# 4robots_MAIN_1_1.net
KiCad netlist of a schematic drawn in EAGLE
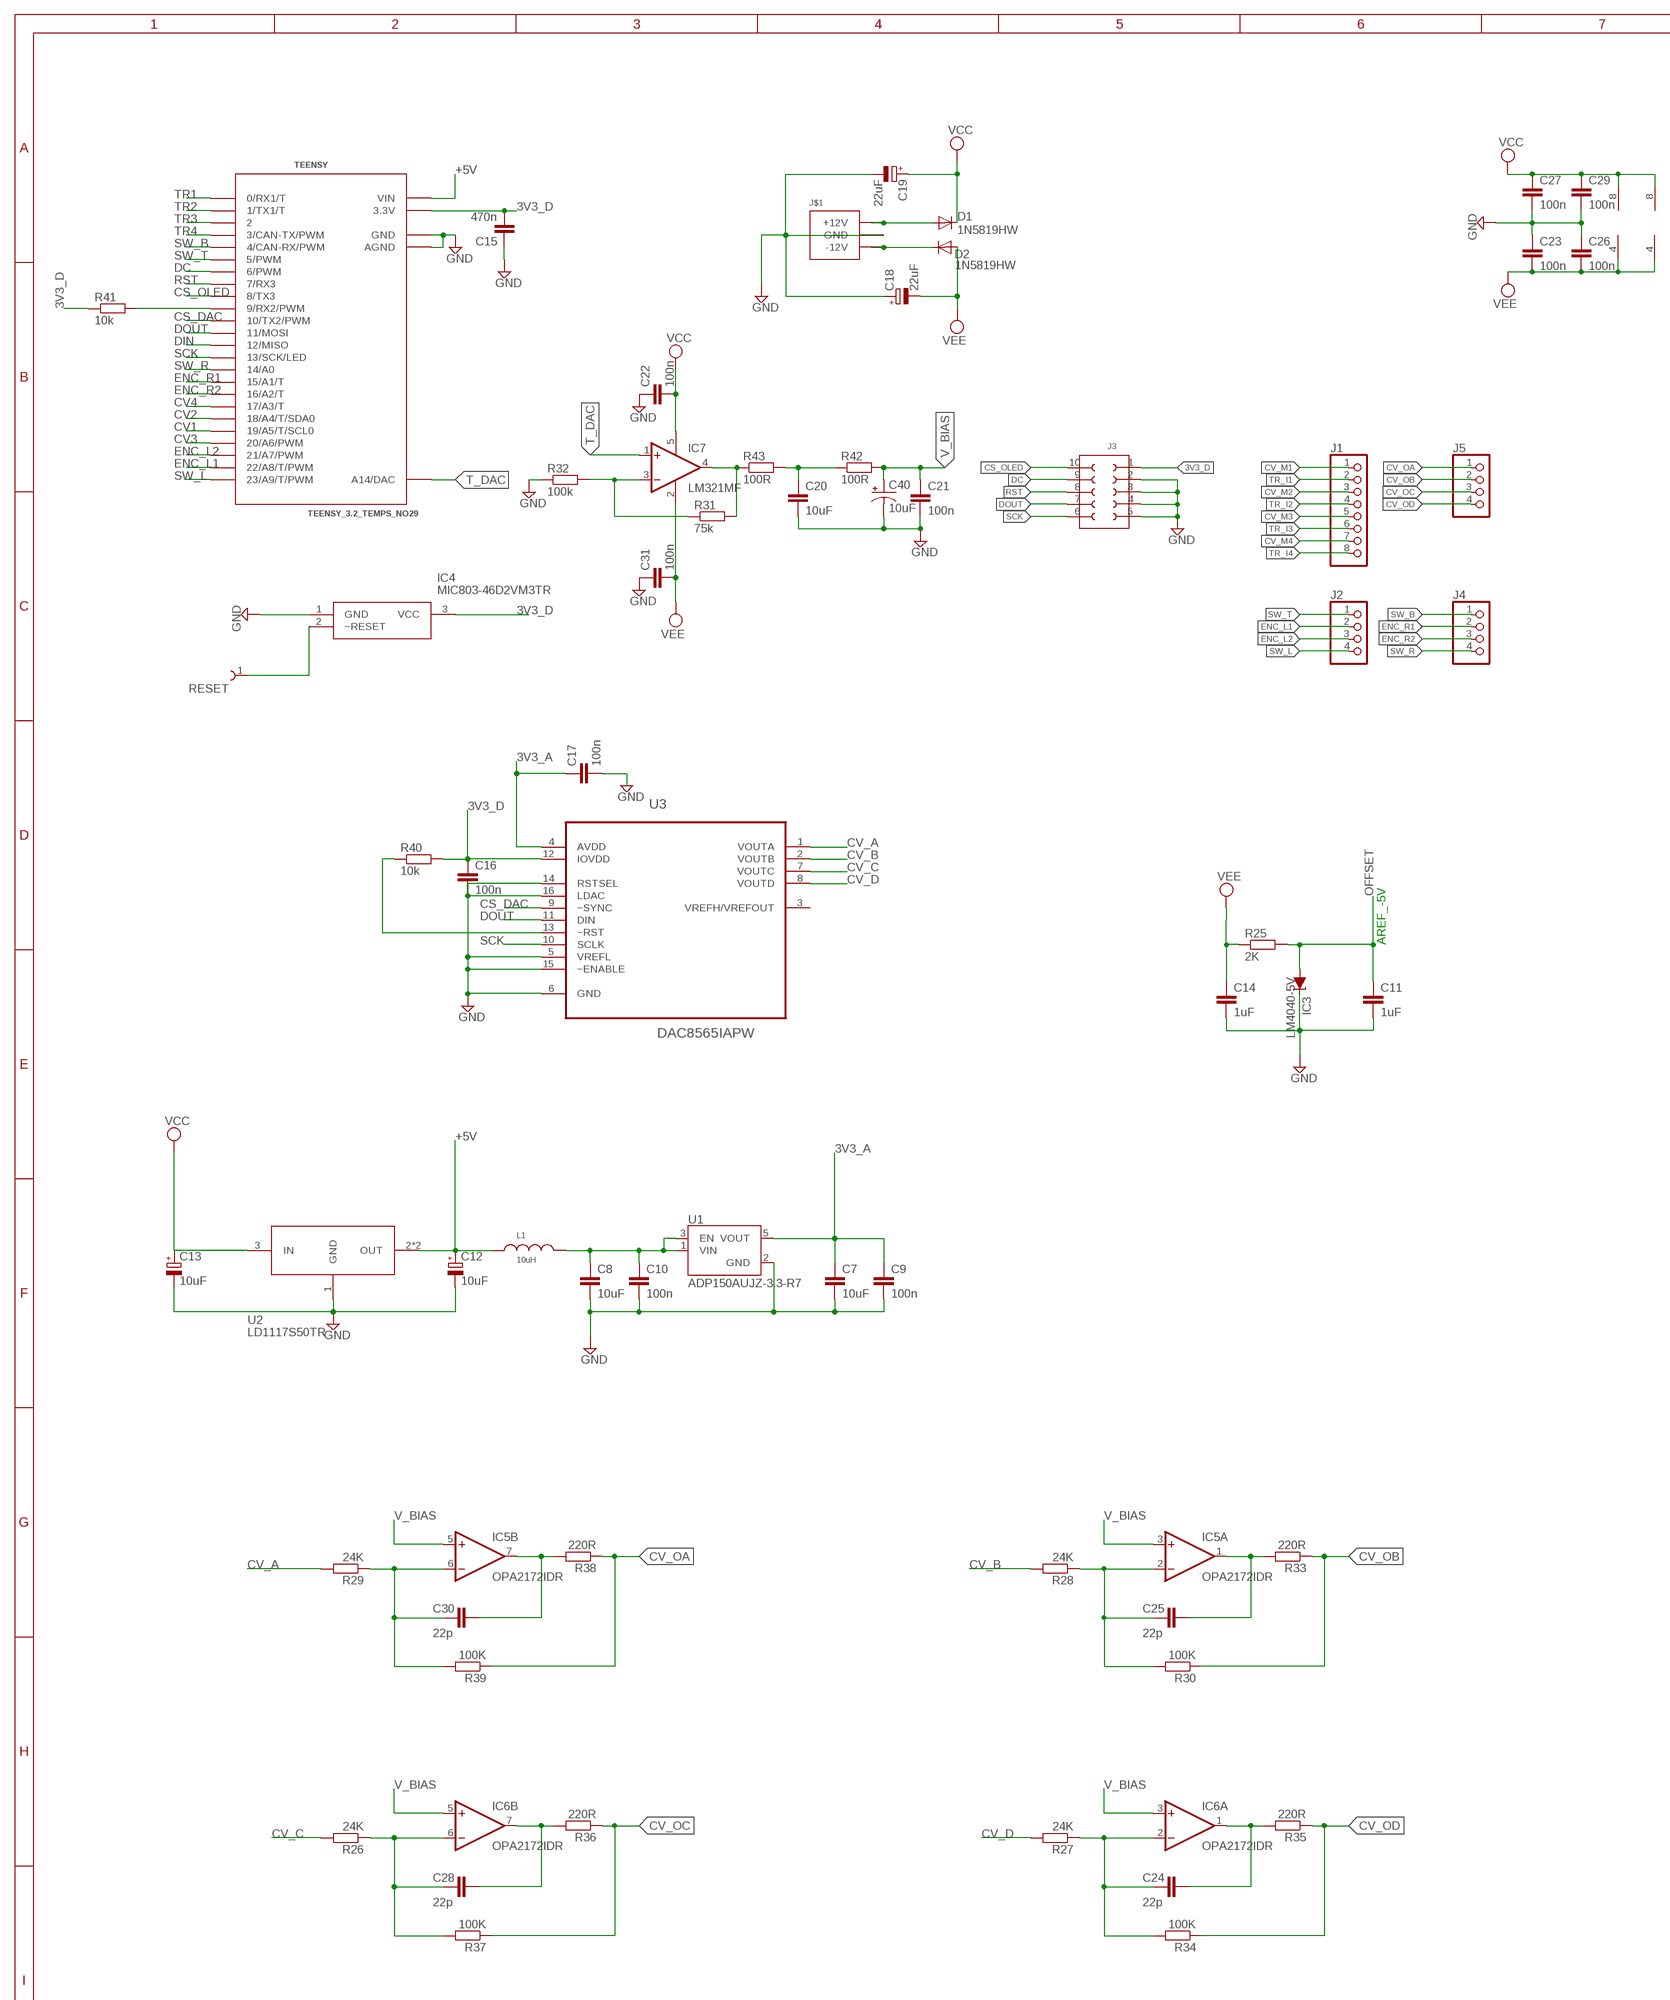
[diagram p0: schematic, sheet 1, part 1 of 2]
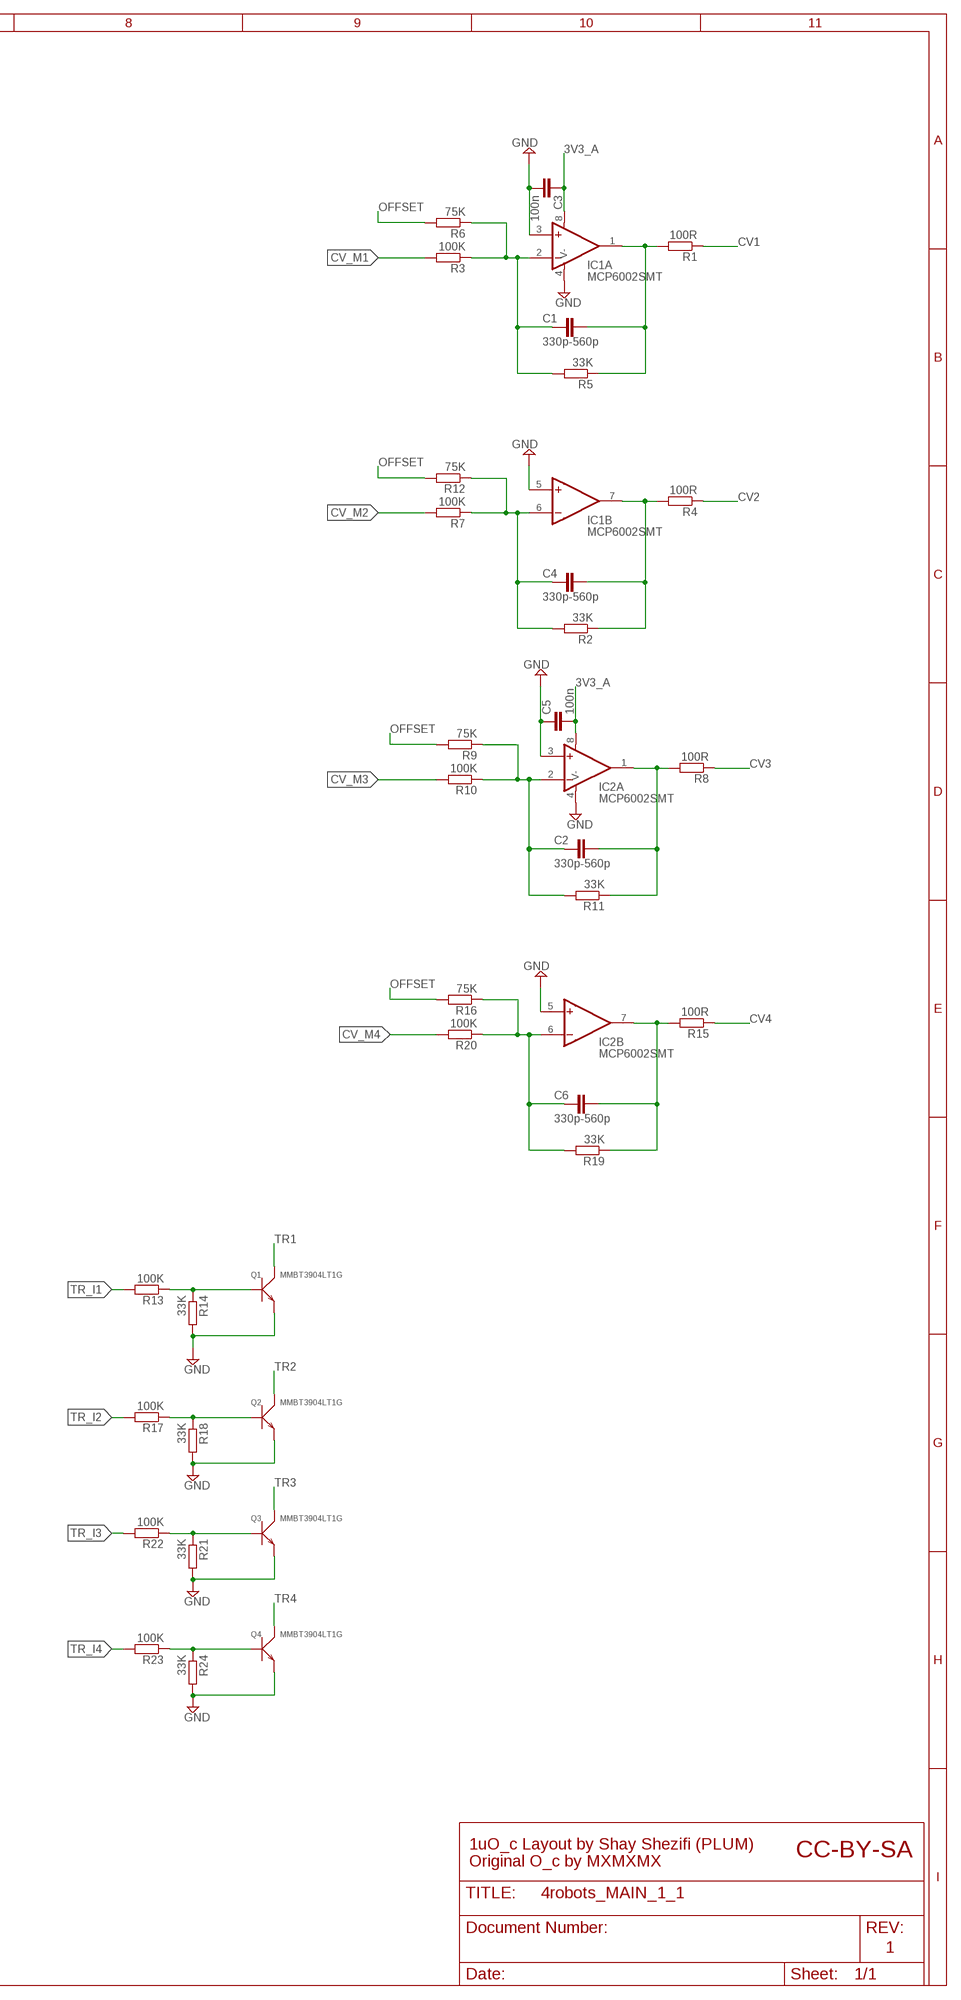
[diagram p1: schematic, sheet 1, part 2 of 2]

(export (version "E")
  (design (tool "Eeschema 10.0.6"))
  (components
    (comp (ref "C1")
      (value "330p-560p")
      (footprint "eagle-import:C0603")
      (libsource (lib "eagle-import") (part "C-EUC0603"))
    )
    (comp (ref "C2")
      (value "330p-560p")
      (footprint "eagle-import:C0603")
      (libsource (lib "eagle-import") (part "C-EUC0603"))
    )
    (comp (ref "C3")
      (value "100n")
      (footprint "eagle-import:C0603")
      (libsource (lib "eagle-import") (part "C-EUC0603"))
    )
    (comp (ref "C4")
      (value "330p-560p")
      (footprint "eagle-import:C0603")
      (libsource (lib "eagle-import") (part "C-EUC0603"))
    )
    (comp (ref "C5")
      (value "100n")
      (footprint "eagle-import:C0603")
      (libsource (lib "eagle-import") (part "C-EUC0603"))
    )
    (comp (ref "C6")
      (value "330p-560p")
      (footprint "eagle-import:C0603")
      (libsource (lib "eagle-import") (part "C-EUC0603"))
    )
    (comp (ref "C7")
      (value "10uF")
      (footprint "eagle-import:C1206K")
      (libsource (lib "eagle-import") (part "C-EUC1206K"))
    )
    (comp (ref "C8")
      (value "10uF")
      (footprint "eagle-import:C1206K")
      (libsource (lib "eagle-import") (part "C-EUC1206K"))
    )
    (comp (ref "C9")
      (value "100n")
      (footprint "eagle-import:C0603")
      (libsource (lib "eagle-import") (part "C-EUC0603"))
    )
    (comp (ref "C10")
      (value "100n")
      (footprint "eagle-import:C0603")
      (libsource (lib "eagle-import") (part "C-EUC0603"))
    )
    (comp (ref "C11")
      (value "1uF")
      (footprint "eagle-import:C0603")
      (libsource (lib "eagle-import") (part "C-EUC0603"))
    )
    (comp (ref "C12")
      (value "10uF")
      (footprint "eagle-import:PANASONIC_B")
      (libsource (lib "eagle-import") (part "CPOL-EUB"))
    )
    (comp (ref "C13")
      (value "10uF")
      (footprint "eagle-import:PANASONIC_B")
      (libsource (lib "eagle-import") (part "CPOL-EUB"))
    )
    (comp (ref "C14")
      (value "1uF")
      (footprint "eagle-import:C0603")
      (libsource (lib "eagle-import") (part "C-EUC0603"))
    )
    (comp (ref "C15")
      (value "470n")
      (footprint "eagle-import:C0603")
      (libsource (lib "eagle-import") (part "C-EUC0603"))
    )
    (comp (ref "C16")
      (value "100n")
      (footprint "eagle-import:C0603")
      (libsource (lib "eagle-import") (part "C-EUC0603"))
    )
    (comp (ref "C17")
      (value "100n")
      (footprint "eagle-import:C0603")
      (libsource (lib "eagle-import") (part "C-EUC0603"))
    )
    (comp (ref "C18")
      (value "22uF")
      (footprint "eagle-import:PANASONIC_C")
      (libsource (lib "eagle-import") (part "CPOL-EUC"))
    )
    (comp (ref "C19")
      (value "22uF")
      (footprint "eagle-import:PANASONIC_C")
      (libsource (lib "eagle-import") (part "CPOL-EUC"))
    )
    (comp (ref "C20")
      (value "10uF")
      (footprint "eagle-import:C0603")
      (libsource (lib "eagle-import") (part "C-EUC0603"))
    )
    (comp (ref "C21")
      (value "100n")
      (footprint "eagle-import:C0603")
      (libsource (lib "eagle-import") (part "C-EUC0603"))
    )
    (comp (ref "C22")
      (value "100n")
      (footprint "eagle-import:C0603")
      (libsource (lib "eagle-import") (part "C-EUC0603"))
    )
    (comp (ref "C23")
      (value "100n")
      (footprint "eagle-import:C0603")
      (libsource (lib "eagle-import") (part "C-EUC0603"))
    )
    (comp (ref "C24")
      (value "22p")
      (footprint "eagle-import:C0603")
      (libsource (lib "eagle-import") (part "C-EUC0603"))
    )
    (comp (ref "C25")
      (value "22p")
      (footprint "eagle-import:C0603")
      (libsource (lib "eagle-import") (part "C-EUC0603"))
    )
    (comp (ref "C26")
      (value "100n")
      (footprint "eagle-import:C0603")
      (libsource (lib "eagle-import") (part "C-EUC0603"))
    )
    (comp (ref "C27")
      (value "100n")
      (footprint "eagle-import:C0603")
      (libsource (lib "eagle-import") (part "C-EUC0603"))
    )
    (comp (ref "C28")
      (value "22p")
      (footprint "eagle-import:C0603")
      (libsource (lib "eagle-import") (part "C-EUC0603"))
    )
    (comp (ref "C29")
      (value "100n")
      (footprint "eagle-import:C0603")
      (libsource (lib "eagle-import") (part "C-EUC0603"))
    )
    (comp (ref "C30")
      (value "22p")
      (footprint "eagle-import:C0603")
      (libsource (lib "eagle-import") (part "C-EUC0603"))
    )
    (comp (ref "C31")
      (value "100n")
      (footprint "eagle-import:C0603")
      (libsource (lib "eagle-import") (part "C-EUC0603"))
    )
    (comp (ref "C40")
      (value "10uF")
      (footprint "eagle-import:PANASONIC_A")
      (libsource (lib "eagle-import") (part "CPOL-USA"))
    )
    (comp (ref "D1")
      (value "1N5819HW")
      (footprint "eagle-import:DIODE_SOD123")
      (libsource (lib "eagle-import") (part "DIODE_DIODE-SOD123"))
    )
    (comp (ref "D2")
      (value "1N5819HW")
      (footprint "eagle-import:DIODE_SOD123")
      (libsource (lib "eagle-import") (part "DIODE_DIODE-SOD123"))
    )
    (comp (ref "IC1")
      (value "MCP6002SMT")
      (footprint "eagle-import:SOIC8")
      (libsource (lib "eagle-import") (part "MCP6002SMT"))
    )
    (comp (ref "IC2")
      (value "MCP6002SMT")
      (footprint "eagle-import:SOIC8")
      (libsource (lib "eagle-import") (part "MCP6002SMT"))
    )
    (comp (ref "IC3")
      (value "LM4040-5V")
      (footprint "eagle-import:DBZ_R-PDSO-G3")
      (libsource (lib "eagle-import") (part "LM4041DBZB12"))
    )
    (comp (ref "IC4")
      (value "MIC803-46D2VM3TR")
      (footprint "eagle-import:SOT95P230X110-3N")
      (libsource (lib "eagle-import") (part "MIC803-46D2VM3TR"))
    )
    (comp (ref "IC5")
      (value "OPA2172IDR")
      (footprint "eagle-import:SO08")
      (libsource (lib "eagle-import") (part "TL072D"))
    )
    (comp (ref "IC6")
      (value "OPA2172IDR")
      (footprint "eagle-import:SO08")
      (libsource (lib "eagle-import") (part "TL072D"))
    )
    (comp (ref "IC7")
      (value "LM321MF")
      (footprint "eagle-import:SOT23-5")
      (libsource (lib "eagle-import") (part "LM321?MF"))
    )
    (comp (ref "J$1")
      (value "POWER_SIMPLE10")
      (footprint "eagle-import:POWER_10")
      (libsource (lib "eagle-import") (part "POWER_SIMPLE10"))
    )
    (comp (ref "J1")
      (value "PINHD-1X8")
      (footprint "eagle-import:1X08")
      (libsource (lib "eagle-import") (part "PINHD-1X8"))
    )
    (comp (ref "J2")
      (value "PINHD-1X4")
      (footprint "eagle-import:1X04")
      (libsource (lib "eagle-import") (part "PINHD-1X4"))
    )
    (comp (ref "J3")
      (value "61301021121")
      (footprint "eagle-import:61301021121")
      (libsource (lib "eagle-import") (part "61301021121"))
    )
    (comp (ref "J4")
      (value "PINHD-1X4")
      (footprint "eagle-import:1X04")
      (libsource (lib "eagle-import") (part "PINHD-1X4"))
    )
    (comp (ref "J5")
      (value "PINHD-1X4")
      (footprint "eagle-import:1X04")
      (libsource (lib "eagle-import") (part "PINHD-1X4"))
    )
    (comp (ref "L1")
      (value "10uH")
      (footprint "eagle-import:WE-LQ_M")
      (libsource (lib "eagle-import") (part "WE-LQ_1210_744032001"))
    )
    (comp (ref "Q1")
      (value "MMBT3904LT1G")
      (footprint "eagle-import:SOT-23")
      (libsource (lib "eagle-import") (part "SMD-TRANSISTORS-NPN-40V-200MA-MMBT3904LT1G(SOT-23)"))
    )
    (comp (ref "Q2")
      (value "MMBT3904LT1G")
      (footprint "eagle-import:SOT-23")
      (libsource (lib "eagle-import") (part "SMD-TRANSISTORS-NPN-40V-200MA-MMBT3904LT1G(SOT-23)"))
    )
    (comp (ref "Q3")
      (value "MMBT3904LT1G")
      (footprint "eagle-import:SOT-23")
      (libsource (lib "eagle-import") (part "SMD-TRANSISTORS-NPN-40V-200MA-MMBT3904LT1G(SOT-23)"))
    )
    (comp (ref "Q4")
      (value "MMBT3904LT1G")
      (footprint "eagle-import:SOT-23")
      (libsource (lib "eagle-import") (part "SMD-TRANSISTORS-NPN-40V-200MA-MMBT3904LT1G(SOT-23)"))
    )
    (comp (ref "R1")
      (value "100R")
      (footprint "eagle-import:R0603")
      (libsource (lib "eagle-import") (part "R-EU_R0603"))
    )
    (comp (ref "R2")
      (value "33K")
      (footprint "eagle-import:R0603")
      (libsource (lib "eagle-import") (part "R-EU_R0603"))
    )
    (comp (ref "R3")
      (value "100K")
      (footprint "eagle-import:R0603")
      (libsource (lib "eagle-import") (part "R-EU_R0603"))
    )
    (comp (ref "R4")
      (value "100R")
      (footprint "eagle-import:R0603")
      (libsource (lib "eagle-import") (part "R-EU_R0603"))
    )
    (comp (ref "R5")
      (value "33K")
      (footprint "eagle-import:R0603")
      (libsource (lib "eagle-import") (part "R-EU_R0603"))
    )
    (comp (ref "R6")
      (value "75K")
      (footprint "eagle-import:R0603")
      (libsource (lib "eagle-import") (part "R-EU_R0603"))
    )
    (comp (ref "R7")
      (value "100K")
      (footprint "eagle-import:R0603")
      (libsource (lib "eagle-import") (part "R-EU_R0603"))
    )
    (comp (ref "R8")
      (value "100R")
      (footprint "eagle-import:R0603")
      (libsource (lib "eagle-import") (part "R-EU_R0603"))
    )
    (comp (ref "R9")
      (value "75K")
      (footprint "eagle-import:R0603")
      (libsource (lib "eagle-import") (part "R-EU_R0603"))
    )
    (comp (ref "R10")
      (value "100K")
      (footprint "eagle-import:R0603")
      (libsource (lib "eagle-import") (part "R-EU_R0603"))
    )
    (comp (ref "R11")
      (value "33K")
      (footprint "eagle-import:R0603")
      (libsource (lib "eagle-import") (part "R-EU_R0603"))
    )
    (comp (ref "R12")
      (value "75K")
      (footprint "eagle-import:R0603")
      (libsource (lib "eagle-import") (part "R-EU_R0603"))
    )
    (comp (ref "R13")
      (value "100K")
      (footprint "eagle-import:R0603")
      (libsource (lib "eagle-import") (part "R-EU_R0603"))
    )
    (comp (ref "R14")
      (value "33K")
      (footprint "eagle-import:R0603")
      (libsource (lib "eagle-import") (part "R-EU_R0603"))
    )
    (comp (ref "R15")
      (value "100R")
      (footprint "eagle-import:R0603")
      (libsource (lib "eagle-import") (part "R-EU_R0603"))
    )
    (comp (ref "R16")
      (value "75K")
      (footprint "eagle-import:R0603")
      (libsource (lib "eagle-import") (part "R-EU_R0603"))
    )
    (comp (ref "R17")
      (value "100K")
      (footprint "eagle-import:R0603")
      (libsource (lib "eagle-import") (part "R-EU_R0603"))
    )
    (comp (ref "R18")
      (value "33K")
      (footprint "eagle-import:R0603")
      (libsource (lib "eagle-import") (part "R-EU_R0603"))
    )
    (comp (ref "R19")
      (value "33K")
      (footprint "eagle-import:R0603")
      (libsource (lib "eagle-import") (part "R-EU_R0603"))
    )
    (comp (ref "R20")
      (value "100K")
      (footprint "eagle-import:R0603")
      (libsource (lib "eagle-import") (part "R-EU_R0603"))
    )
    (comp (ref "R21")
      (value "33K")
      (footprint "eagle-import:R0603")
      (libsource (lib "eagle-import") (part "R-EU_R0603"))
    )
    (comp (ref "R22")
      (value "100K")
      (footprint "eagle-import:R0603")
      (libsource (lib "eagle-import") (part "R-EU_R0603"))
    )
    (comp (ref "R23")
      (value "100K")
      (footprint "eagle-import:R0603")
      (libsource (lib "eagle-import") (part "R-EU_R0603"))
    )
    (comp (ref "R24")
      (value "33K")
      (footprint "eagle-import:R0603")
      (libsource (lib "eagle-import") (part "R-EU_R0603"))
    )
    (comp (ref "R25")
      (value "2K")
      (footprint "eagle-import:R0603")
      (libsource (lib "eagle-import") (part "R-EU_R0603"))
    )
    (comp (ref "R26")
      (value "24K")
      (footprint "eagle-import:R0603")
      (libsource (lib "eagle-import") (part "R-EU_R0603"))
    )
    (comp (ref "R27")
      (value "24K")
      (footprint "eagle-import:R0603")
      (libsource (lib "eagle-import") (part "R-EU_R0603"))
    )
    (comp (ref "R28")
      (value "24K")
      (footprint "eagle-import:R0603")
      (libsource (lib "eagle-import") (part "R-EU_R0603"))
    )
    (comp (ref "R29")
      (value "24K")
      (footprint "eagle-import:R0603")
      (libsource (lib "eagle-import") (part "R-EU_R0603"))
    )
    (comp (ref "R30")
      (value "100K")
      (footprint "eagle-import:R0603")
      (libsource (lib "eagle-import") (part "R-EU_R0603"))
    )
    (comp (ref "R31")
      (value "75k")
      (footprint "eagle-import:R0603")
      (libsource (lib "eagle-import") (part "R-EU_R0603"))
    )
    (comp (ref "R32")
      (value "100k")
      (footprint "eagle-import:R0603")
      (libsource (lib "eagle-import") (part "R-EU_R0603"))
    )
    (comp (ref "R33")
      (value "220R")
      (footprint "eagle-import:R0603")
      (libsource (lib "eagle-import") (part "R-EU_R0603"))
    )
    (comp (ref "R34")
      (value "100K")
      (footprint "eagle-import:R0603")
      (libsource (lib "eagle-import") (part "R-EU_R0603"))
    )
    (comp (ref "R35")
      (value "220R")
      (footprint "eagle-import:R0603")
      (libsource (lib "eagle-import") (part "R-EU_R0603"))
    )
    (comp (ref "R36")
      (value "220R")
      (footprint "eagle-import:R0603")
      (libsource (lib "eagle-import") (part "R-EU_R0603"))
    )
    (comp (ref "R37")
      (value "100K")
      (footprint "eagle-import:R0603")
      (libsource (lib "eagle-import") (part "R-EU_R0603"))
    )
    (comp (ref "R38")
      (value "220R")
      (footprint "eagle-import:R0603")
      (libsource (lib "eagle-import") (part "R-EU_R0603"))
    )
    (comp (ref "R39")
      (value "100K")
      (footprint "eagle-import:R0603")
      (libsource (lib "eagle-import") (part "R-EU_R0603"))
    )
    (comp (ref "R40")
      (value "10k")
      (footprint "eagle-import:R0603")
      (libsource (lib "eagle-import") (part "R-EU_R0603"))
    )
    (comp (ref "R41")
      (value "10k")
      (footprint "eagle-import:R0603")
      (libsource (lib "eagle-import") (part "R-EU_R0603"))
    )
    (comp (ref "R42")
      (value "100R")
      (footprint "eagle-import:R0603")
      (libsource (lib "eagle-import") (part "R-EU_R0603"))
    )
    (comp (ref "R43")
      (value "100R")
      (footprint "eagle-import:R0603")
      (libsource (lib "eagle-import") (part "R-EU_R0603"))
    )
    (comp (ref "RESET")
      (value "61300111121")
      (footprint "eagle-import:61300111121")
      (libsource (lib "eagle-import") (part "61300111121"))
    )
    (comp (ref "TEENSY")
      (value "TEENSY_3.2_TEMPS_NO29")
      (footprint "eagle-import:TEENSY_3.2_TEMPS_NO29")
      (libsource (lib "eagle-import") (part "TEENSY_3.2_TEMPS_NO29"))
    )
    (comp (ref "U1")
      (value "ADP150AUJZ-3.3-R7")
      (footprint "eagle-import:SOT95P280X100-5N")
      (fields (field (name "MF") "Analog Devices") (field (name "MP") "ADP150AUJZ-2.0-R7"))
      (libsource (lib "eagle-import") (part "ADP150AUJZ-3.3-R7"))
    )
    (comp (ref "U2")
      (value "LD1117S50TR")
      (footprint "eagle-import:SOT223")
      (fields (field (name "MF") "STMicroelectronics"))
      (libsource (lib "eagle-import") (part "LD1117S50TR"))
    )
    (comp (ref "U3")
      (value "DAC8565IAPW")
      (footprint "eagle-import:SOP65P640X120-16N")
      (fields (field (name "MF") "Texas Instruments"))
      (libsource (lib "eagle-import") (part "DAC8565IAPW"))
    )
  )
  (nets
    (net (code "1") (name "/+5V") (class "Default")
      (node (ref "C12") (pin "+") (pinfunction "+_+") (pintype "passive"))
      (node (ref "L1") (pin "1") (pinfunction "1_1") (pintype "passive"))
      (node (ref "TEENSY") (pin "VIN") (pinfunction "VIN_VIN") (pintype "power_in"))
      (node (ref "U2") (pin "2") (pinfunction "OUT_2") (pintype "output"))
      (node (ref "U2") (pin "4") (pinfunction "OUT_4") (pintype "output"))
    )
    (net (code "2") (name "/3V3_A") (class "Default")
      (node (ref "C17") (pin "1") (pinfunction "1_1") (pintype "passive"))
      (node (ref "C3") (pin "1") (pinfunction "1_1") (pintype "passive"))
      (node (ref "C5") (pin "2") (pinfunction "2_2") (pintype "passive"))
      (node (ref "C7") (pin "1") (pinfunction "1_1") (pintype "passive"))
      (node (ref "C9") (pin "1") (pinfunction "1_1") (pintype "passive"))
      (node (ref "IC1") (pin "8") (pinfunction "V+_8") (pintype "power_in"))
      (node (ref "IC2") (pin "8") (pinfunction "V+_8") (pintype "power_in"))
      (node (ref "U1") (pin "5") (pinfunction "VOUT_5") (pintype "output"))
      (node (ref "U3") (pin "4") (pinfunction "AVDD_4") (pintype "power_in"))
    )
    (net (code "3") (name "/CS_DAC") (class "Default")
      (node (ref "TEENSY") (pin "10") (pinfunction "10/TX2/PWM_10") (pintype "bidirectional"))
      (node (ref "U3") (pin "9") (pinfunction "~{SYNC}_9") (pintype "input"))
    )
    (net (code "4") (name "/CV1") (class "Default")
      (node (ref "R1") (pin "1") (pinfunction "1_1") (pintype "passive"))
      (node (ref "TEENSY") (pin "19/A5") (pinfunction "19/A5/T/SCL0_19/A5") (pintype "bidirectional"))
    )
    (net (code "5") (name "/CV2") (class "Default")
      (node (ref "R4") (pin "1") (pinfunction "1_1") (pintype "passive"))
      (node (ref "TEENSY") (pin "18/A4") (pinfunction "18/A4/T/SDA0_18/A4") (pintype "bidirectional"))
    )
    (net (code "6") (name "/CV3") (class "Default")
      (node (ref "R8") (pin "1") (pinfunction "1_1") (pintype "passive"))
      (node (ref "TEENSY") (pin "20/A6") (pinfunction "20/A6/PWM_20/A6") (pintype "bidirectional"))
    )
    (net (code "7") (name "/CV4") (class "Default")
      (node (ref "R15") (pin "1") (pinfunction "1_1") (pintype "passive"))
      (node (ref "TEENSY") (pin "17/A3") (pinfunction "17/A3/T_17/A3") (pintype "bidirectional"))
    )
    (net (code "8") (name "/CV_A") (class "Default")
      (node (ref "R29") (pin "2") (pinfunction "2_2") (pintype "passive"))
      (node (ref "U3") (pin "1") (pinfunction "VOUTA_1") (pintype "output"))
    )
    (net (code "9") (name "/CV_B") (class "Default")
      (node (ref "R28") (pin "2") (pinfunction "2_2") (pintype "passive"))
      (node (ref "U3") (pin "2") (pinfunction "VOUTB_2") (pintype "output"))
    )
    (net (code "10") (name "/CV_C") (class "Default")
      (node (ref "R26") (pin "2") (pinfunction "2_2") (pintype "passive"))
      (node (ref "U3") (pin "7") (pinfunction "VOUTC_7") (pintype "output"))
    )
    (net (code "11") (name "/CV_D") (class "Default")
      (node (ref "R27") (pin "2") (pinfunction "2_2") (pintype "passive"))
      (node (ref "U3") (pin "8") (pinfunction "VOUTD_8") (pintype "output"))
    )
    (net (code "12") (name "/DIN") (class "Default")
      (node (ref "TEENSY") (pin "12") (pinfunction "12/MISO_12") (pintype "bidirectional"))
    )
    (net (code "13") (name "/OFFSET") (class "Default")
      (node (ref "C11") (pin "1") (pinfunction "1_1") (pintype "passive"))
      (node (ref "IC3") (pin "2") (pinfunction "A_2") (pintype "passive"))
      (node (ref "R12") (pin "2") (pinfunction "2_2") (pintype "passive"))
      (node (ref "R16") (pin "2") (pinfunction "2_2") (pintype "passive"))
      (node (ref "R25") (pin "2") (pinfunction "2_2") (pintype "passive"))
      (node (ref "R6") (pin "2") (pinfunction "2_2") (pintype "passive"))
      (node (ref "R9") (pin "2") (pinfunction "2_2") (pintype "passive"))
    )
    (net (code "14") (name "/TR1") (class "Default")
      (node (ref "Q1") (pin "3") (pinfunction "C_3") (pintype "passive"))
      (node (ref "TEENSY") (pin "0") (pinfunction "0/RX1/T_0") (pintype "bidirectional"))
    )
    (net (code "15") (name "/TR2") (class "Default")
      (node (ref "Q2") (pin "3") (pinfunction "C_3") (pintype "passive"))
      (node (ref "TEENSY") (pin "1") (pinfunction "1/TX1/T_1") (pintype "bidirectional"))
    )
    (net (code "16") (name "/TR3") (class "Default")
      (node (ref "Q3") (pin "3") (pinfunction "C_3") (pintype "passive"))
      (node (ref "TEENSY") (pin "2") (pinfunction "2_2") (pintype "bidirectional"))
    )
    (net (code "17") (name "/TR4") (class "Default")
      (node (ref "Q4") (pin "3") (pinfunction "C_3") (pintype "passive"))
      (node (ref "TEENSY") (pin "3") (pinfunction "3/CAN-TX/PWM_3") (pintype "bidirectional"))
    )
    (net (code "18") (name "3V3_D") (class "Default")
      (node (ref "C15") (pin "2") (pinfunction "2_2") (pintype "passive"))
      (node (ref "C16") (pin "1") (pinfunction "1_1") (pintype "passive"))
      (node (ref "IC4") (pin "3") (pinfunction "VCC_3") (pintype "bidirectional"))
      (node (ref "J3") (pin "1") (pinfunction "1_1") (pintype "passive"))
      (node (ref "R40") (pin "2") (pinfunction "2_2") (pintype "passive"))
      (node (ref "R41") (pin "1") (pinfunction "1_1") (pintype "passive"))
      (node (ref "TEENSY") (pin "3.3V") (pinfunction "3.3V_3.3V") (pintype "power_in"))
      (node (ref "U3") (pin "12") (pinfunction "IOVDD_12") (pintype "power_in"))
    )
    (net (code "19") (name "CS_OLED") (class "Default")
      (node (ref "J3") (pin "10") (pinfunction "10_10") (pintype "passive"))
      (node (ref "TEENSY") (pin "8") (pinfunction "8/TX3_8") (pintype "bidirectional"))
    )
    (net (code "20") (name "CV_M1") (class "Default")
      (node (ref "J1") (pin "1") (pinfunction "1_1") (pintype "passive"))
      (node (ref "R3") (pin "2") (pinfunction "2_2") (pintype "passive"))
    )
    (net (code "21") (name "CV_M2") (class "Default")
      (node (ref "J1") (pin "3") (pinfunction "3_3") (pintype "passive"))
      (node (ref "R7") (pin "2") (pinfunction "2_2") (pintype "passive"))
    )
    (net (code "22") (name "CV_M3") (class "Default")
      (node (ref "J1") (pin "5") (pinfunction "5_5") (pintype "passive"))
      (node (ref "R10") (pin "2") (pinfunction "2_2") (pintype "passive"))
    )
    (net (code "23") (name "CV_M4") (class "Default")
      (node (ref "J1") (pin "7") (pinfunction "7_7") (pintype "passive"))
      (node (ref "R20") (pin "2") (pinfunction "2_2") (pintype "passive"))
    )
    (net (code "24") (name "CV_OA") (class "Default")
      (node (ref "J5") (pin "1") (pinfunction "1_1") (pintype "passive"))
      (node (ref "R38") (pin "1") (pinfunction "1_1") (pintype "passive"))
      (node (ref "R39") (pin "1") (pinfunction "1_1") (pintype "passive"))
    )
    (net (code "25") (name "CV_OB") (class "Default")
      (node (ref "J5") (pin "2") (pinfunction "2_2") (pintype "passive"))
      (node (ref "R30") (pin "1") (pinfunction "1_1") (pintype "passive"))
      (node (ref "R33") (pin "1") (pinfunction "1_1") (pintype "passive"))
    )
    (net (code "26") (name "CV_OC") (class "Default")
      (node (ref "J5") (pin "3") (pinfunction "3_3") (pintype "passive"))
      (node (ref "R36") (pin "1") (pinfunction "1_1") (pintype "passive"))
      (node (ref "R37") (pin "1") (pinfunction "1_1") (pintype "passive"))
    )
    (net (code "27") (name "CV_OD") (class "Default")
      (node (ref "J5") (pin "4") (pinfunction "4_4") (pintype "passive"))
      (node (ref "R34") (pin "1") (pinfunction "1_1") (pintype "passive"))
      (node (ref "R35") (pin "1") (pinfunction "1_1") (pintype "passive"))
    )
    (net (code "28") (name "DC") (class "Default")
      (node (ref "J3") (pin "9") (pinfunction "9_9") (pintype "passive"))
      (node (ref "TEENSY") (pin "6") (pinfunction "6/PWM_6") (pintype "bidirectional"))
    )
    (net (code "29") (name "DOUT") (class "Default")
      (node (ref "J3") (pin "7") (pinfunction "7_7") (pintype "passive"))
      (node (ref "TEENSY") (pin "11") (pinfunction "11/MOSI_11") (pintype "bidirectional"))
      (node (ref "U3") (pin "11") (pinfunction "DIN_11") (pintype "input"))
    )
    (net (code "30") (name "ENC_L1") (class "Default")
      (node (ref "J2") (pin "2") (pinfunction "2_2") (pintype "passive"))
      (node (ref "TEENSY") (pin "22/A8") (pinfunction "22/A8/T/PWM_22/A8") (pintype "bidirectional"))
    )
    (net (code "31") (name "ENC_L2") (class "Default")
      (node (ref "J2") (pin "3") (pinfunction "3_3") (pintype "passive"))
      (node (ref "TEENSY") (pin "21/A7") (pinfunction "21/A7/PWM_21/A7") (pintype "bidirectional"))
    )
    (net (code "32") (name "ENC_R1") (class "Default")
      (node (ref "J4") (pin "2") (pinfunction "2_2") (pintype "passive"))
      (node (ref "TEENSY") (pin "15/A1") (pinfunction "15/A1/T_15/A1") (pintype "bidirectional"))
    )
    (net (code "33") (name "ENC_R2") (class "Default")
      (node (ref "J4") (pin "3") (pinfunction "3_3") (pintype "passive"))
      (node (ref "TEENSY") (pin "16/A2") (pinfunction "16/A2/T_16/A2") (pintype "bidirectional"))
    )
    (net (code "34") (name "GND") (class "Default")
      (node (ref "C10") (pin "2") (pinfunction "2_2") (pintype "passive"))
      (node (ref "C11") (pin "2") (pinfunction "2_2") (pintype "passive"))
      (node (ref "C12") (pin "-") (pinfunction "-_-") (pintype "passive"))
      (node (ref "C13") (pin "-") (pinfunction "-_-") (pintype "passive"))
      (node (ref "C14") (pin "2") (pinfunction "2_2") (pintype "passive"))
      (node (ref "C15") (pin "1") (pinfunction "1_1") (pintype "passive"))
      (node (ref "C16") (pin "2") (pinfunction "2_2") (pintype "passive"))
      (node (ref "C17") (pin "2") (pinfunction "2_2") (pintype "passive"))
      (node (ref "C18") (pin "+") (pinfunction "+_+") (pintype "passive"))
      (node (ref "C19") (pin "-") (pinfunction "-_-") (pintype "passive"))
      (node (ref "C20") (pin "2") (pinfunction "2_2") (pintype "passive"))
      (node (ref "C21") (pin "2") (pinfunction "2_2") (pintype "passive"))
      (node (ref "C22") (pin "1") (pinfunction "1_1") (pintype "passive"))
      (node (ref "C23") (pin "1") (pinfunction "1_1") (pintype "passive"))
      (node (ref "C26") (pin "1") (pinfunction "1_1") (pintype "passive"))
      (node (ref "C27") (pin "2") (pinfunction "2_2") (pintype "passive"))
      (node (ref "C29") (pin "2") (pinfunction "2_2") (pintype "passive"))
      (node (ref "C3") (pin "2") (pinfunction "2_2") (pintype "passive"))
      (node (ref "C31") (pin "1") (pinfunction "1_1") (pintype "passive"))
      (node (ref "C40") (pin "-") (pinfunction "-_-") (pintype "passive"))
      (node (ref "C5") (pin "1") (pinfunction "1_1") (pintype "passive"))
      (node (ref "C7") (pin "2") (pinfunction "2_2") (pintype "passive"))
      (node (ref "C8") (pin "2") (pinfunction "2_2") (pintype "passive"))
      (node (ref "C9") (pin "2") (pinfunction "2_2") (pintype "passive"))
      (node (ref "IC1") (pin "3") (pinfunction "+IN_3") (pintype "input"))
      (node (ref "IC1") (pin "4") (pinfunction "V-_4") (pintype "power_in"))
      (node (ref "IC1") (pin "5") (pinfunction "+IN_5") (pintype "input"))
      (node (ref "IC2") (pin "3") (pinfunction "+IN_3") (pintype "input"))
      (node (ref "IC2") (pin "4") (pinfunction "V-_4") (pintype "power_in"))
      (node (ref "IC2") (pin "5") (pinfunction "+IN_5") (pintype "input"))
      (node (ref "IC3") (pin "1") (pinfunction "C_1") (pintype "passive"))
      (node (ref "IC4") (pin "1") (pinfunction "GND_1") (pintype "bidirectional"))
      (node (ref "J$1") (pin "3") (pinfunction "GND_3") (pintype "bidirectional"))
      (node (ref "J$1") (pin "4") (pinfunction "GND_4") (pintype "bidirectional"))
      (node (ref "J$1") (pin "5") (pinfunction "GND_5") (pintype "bidirectional"))
      (node (ref "J$1") (pin "6") (pinfunction "GND_6") (pintype "bidirectional"))
      (node (ref "J$1") (pin "7") (pinfunction "GND_7") (pintype "bidirectional"))
      (node (ref "J$1") (pin "8") (pinfunction "GND_8") (pintype "bidirectional"))
      (node (ref "J3") (pin "2") (pinfunction "2_2") (pintype "passive"))
      (node (ref "J3") (pin "3") (pinfunction "3_3") (pintype "passive"))
      (node (ref "J3") (pin "4") (pinfunction "4_4") (pintype "passive"))
      (node (ref "J3") (pin "5") (pinfunction "5_5") (pintype "passive"))
      (node (ref "Q1") (pin "2") (pinfunction "E_2") (pintype "passive"))
      (node (ref "Q2") (pin "2") (pinfunction "E_2") (pintype "passive"))
      (node (ref "Q3") (pin "2") (pinfunction "E_2") (pintype "passive"))
      (node (ref "Q4") (pin "2") (pinfunction "E_2") (pintype "passive"))
      (node (ref "R14") (pin "2") (pinfunction "2_2") (pintype "passive"))
      (node (ref "R18") (pin "2") (pinfunction "2_2") (pintype "passive"))
      (node (ref "R21") (pin "2") (pinfunction "2_2") (pintype "passive"))
      (node (ref "R24") (pin "2") (pinfunction "2_2") (pintype "passive"))
      (node (ref "R32") (pin "1") (pinfunction "1_1") (pintype "passive"))
      (node (ref "TEENSY") (pin "AGND") (pinfunction "AGND_AGND") (pintype "power_in"))
      (node (ref "TEENSY") (pin "GND") (pinfunction "GND_GND") (pintype "power_in"))
      (node (ref "U1") (pin "2") (pinfunction "GND_2") (pintype "power_in"))
      (node (ref "U2") (pin "1") (pinfunction "GND_1") (pintype "passive"))
      (node (ref "U3") (pin "14") (pinfunction "RSTSEL_14") (pintype "input"))
      (node (ref "U3") (pin "15") (pinfunction "~{ENABLE}_15") (pintype "input"))
      (node (ref "U3") (pin "16") (pinfunction "LDAC_16") (pintype "input"))
      (node (ref "U3") (pin "5") (pinfunction "VREFL_5") (pintype "input"))
      (node (ref "U3") (pin "6") (pinfunction "GND_6") (pintype "passive"))
    )
    (net (code "35") (name "Net-(C20-Pad1)") (class "Default")
      (node (ref "C20") (pin "1") (pinfunction "1_1") (pintype "passive"))
      (node (ref "R42") (pin "1") (pinfunction "1_1") (pintype "passive"))
      (node (ref "R43") (pin "2") (pinfunction "2_2") (pintype "passive"))
    )
    (net (code "36") (name "Net-(D1-PadA)") (class "Default")
      (node (ref "D1") (pin "A") (pinfunction "A_A") (pintype "passive"))
      (node (ref "J$1") (pin "10") (pinfunction "+12V_10") (pintype "bidirectional"))
      (node (ref "J$1") (pin "9") (pinfunction "+12V_9") (pintype "bidirectional"))
    )
    (net (code "37") (name "Net-(D2-PadC)") (class "Default")
      (node (ref "D2") (pin "C") (pinfunction "C_C") (pintype "passive"))
      (node (ref "J$1") (pin "1") (pinfunction "-12V_1") (pintype "bidirectional"))
      (node (ref "J$1") (pin "2") (pinfunction "-12V_2") (pintype "bidirectional"))
    )
    (net (code "38") (name "Net-(IC1A--IN)") (class "Default")
      (node (ref "C1") (pin "2") (pinfunction "2_2") (pintype "passive"))
      (node (ref "IC1") (pin "2") (pinfunction "-IN_2") (pintype "input"))
      (node (ref "R3") (pin "1") (pinfunction "1_1") (pintype "passive"))
      (node (ref "R5") (pin "2") (pinfunction "2_2") (pintype "passive"))
      (node (ref "R6") (pin "1") (pinfunction "1_1") (pintype "passive"))
    )
    (net (code "39") (name "Net-(IC1A-OUT)") (class "Default")
      (node (ref "C1") (pin "1") (pinfunction "1_1") (pintype "passive"))
      (node (ref "IC1") (pin "1") (pinfunction "OUT_1") (pintype "output"))
      (node (ref "R1") (pin "2") (pinfunction "2_2") (pintype "passive"))
      (node (ref "R5") (pin "1") (pinfunction "1_1") (pintype "passive"))
    )
    (net (code "40") (name "Net-(IC1B--IN)") (class "Default")
      (node (ref "C4") (pin "2") (pinfunction "2_2") (pintype "passive"))
      (node (ref "IC1") (pin "6") (pinfunction "-IN_6") (pintype "input"))
      (node (ref "R12") (pin "1") (pinfunction "1_1") (pintype "passive"))
      (node (ref "R2") (pin "2") (pinfunction "2_2") (pintype "passive"))
      (node (ref "R7") (pin "1") (pinfunction "1_1") (pintype "passive"))
    )
    (net (code "41") (name "Net-(IC1B-OUT)") (class "Default")
      (node (ref "C4") (pin "1") (pinfunction "1_1") (pintype "passive"))
      (node (ref "IC1") (pin "7") (pinfunction "OUT_7") (pintype "output"))
      (node (ref "R2") (pin "1") (pinfunction "1_1") (pintype "passive"))
      (node (ref "R4") (pin "2") (pinfunction "2_2") (pintype "passive"))
    )
    (net (code "42") (name "Net-(IC2A--IN)") (class "Default")
      (node (ref "C2") (pin "2") (pinfunction "2_2") (pintype "passive"))
      (node (ref "IC2") (pin "2") (pinfunction "-IN_2") (pintype "input"))
      (node (ref "R10") (pin "1") (pinfunction "1_1") (pintype "passive"))
      (node (ref "R11") (pin "2") (pinfunction "2_2") (pintype "passive"))
      (node (ref "R9") (pin "1") (pinfunction "1_1") (pintype "passive"))
    )
    (net (code "43") (name "Net-(IC2A-OUT)") (class "Default")
      (node (ref "C2") (pin "1") (pinfunction "1_1") (pintype "passive"))
      (node (ref "IC2") (pin "1") (pinfunction "OUT_1") (pintype "output"))
      (node (ref "R11") (pin "1") (pinfunction "1_1") (pintype "passive"))
      (node (ref "R8") (pin "2") (pinfunction "2_2") (pintype "passive"))
    )
    (net (code "44") (name "Net-(IC2B--IN)") (class "Default")
      (node (ref "C6") (pin "2") (pinfunction "2_2") (pintype "passive"))
      (node (ref "IC2") (pin "6") (pinfunction "-IN_6") (pintype "input"))
      (node (ref "R16") (pin "1") (pinfunction "1_1") (pintype "passive"))
      (node (ref "R19") (pin "2") (pinfunction "2_2") (pintype "passive"))
      (node (ref "R20") (pin "1") (pinfunction "1_1") (pintype "passive"))
    )
    (net (code "45") (name "Net-(IC2B-OUT)") (class "Default")
      (node (ref "C6") (pin "1") (pinfunction "1_1") (pintype "passive"))
      (node (ref "IC2") (pin "7") (pinfunction "OUT_7") (pintype "output"))
      (node (ref "R15") (pin "2") (pinfunction "2_2") (pintype "passive"))
      (node (ref "R19") (pin "1") (pinfunction "1_1") (pintype "passive"))
    )
    (net (code "46") (name "Net-(IC4-~{RESET})") (class "Default")
      (node (ref "IC4") (pin "2") (pinfunction "~{RESET}_2") (pintype "bidirectional"))
      (node (ref "RESET") (pin "1") (pinfunction "1_1") (pintype "passive"))
    )
    (net (code "47") (name "Net-(IC5A--IN)") (class "Default")
      (node (ref "C25") (pin "2") (pinfunction "2_2") (pintype "passive"))
      (node (ref "IC5") (pin "2") (pinfunction "-IN_2") (pintype "input"))
      (node (ref "R28") (pin "1") (pinfunction "1_1") (pintype "passive"))
      (node (ref "R30") (pin "2") (pinfunction "2_2") (pintype "passive"))
    )
    (net (code "48") (name "Net-(IC5A-OUT)") (class "Default")
      (node (ref "C25") (pin "1") (pinfunction "1_1") (pintype "passive"))
      (node (ref "IC5") (pin "1") (pinfunction "OUT_1") (pintype "output"))
      (node (ref "R33") (pin "2") (pinfunction "2_2") (pintype "passive"))
    )
    (net (code "49") (name "Net-(IC5B--IN)") (class "Default")
      (node (ref "C30") (pin "2") (pinfunction "2_2") (pintype "passive"))
      (node (ref "IC5") (pin "6") (pinfunction "-IN_6") (pintype "input"))
      (node (ref "R29") (pin "1") (pinfunction "1_1") (pintype "passive"))
      (node (ref "R39") (pin "2") (pinfunction "2_2") (pintype "passive"))
    )
    (net (code "50") (name "Net-(IC5B-OUT)") (class "Default")
      (node (ref "C30") (pin "1") (pinfunction "1_1") (pintype "passive"))
      (node (ref "IC5") (pin "7") (pinfunction "OUT_7") (pintype "output"))
      (node (ref "R38") (pin "2") (pinfunction "2_2") (pintype "passive"))
    )
    (net (code "51") (name "Net-(IC6A--IN)") (class "Default")
      (node (ref "C24") (pin "2") (pinfunction "2_2") (pintype "passive"))
      (node (ref "IC6") (pin "2") (pinfunction "-IN_2") (pintype "input"))
      (node (ref "R27") (pin "1") (pinfunction "1_1") (pintype "passive"))
      (node (ref "R34") (pin "2") (pinfunction "2_2") (pintype "passive"))
    )
    (net (code "52") (name "Net-(IC6A-OUT)") (class "Default")
      (node (ref "C24") (pin "1") (pinfunction "1_1") (pintype "passive"))
      (node (ref "IC6") (pin "1") (pinfunction "OUT_1") (pintype "output"))
      (node (ref "R35") (pin "2") (pinfunction "2_2") (pintype "passive"))
    )
    (net (code "53") (name "Net-(IC6B--IN)") (class "Default")
      (node (ref "C28") (pin "2") (pinfunction "2_2") (pintype "passive"))
      (node (ref "IC6") (pin "6") (pinfunction "-IN_6") (pintype "input"))
      (node (ref "R26") (pin "1") (pinfunction "1_1") (pintype "passive"))
      (node (ref "R37") (pin "2") (pinfunction "2_2") (pintype "passive"))
    )
    (net (code "54") (name "Net-(IC6B-OUT)") (class "Default")
      (node (ref "C28") (pin "1") (pinfunction "1_1") (pintype "passive"))
      (node (ref "IC6") (pin "7") (pinfunction "OUT_7") (pintype "output"))
      (node (ref "R36") (pin "2") (pinfunction "2_2") (pintype "passive"))
    )
    (net (code "55") (name "Net-(IC7--IN)") (class "Default")
      (node (ref "IC7") (pin "3") (pinfunction "-IN_3") (pintype "input"))
      (node (ref "R31") (pin "1") (pinfunction "1_1") (pintype "passive"))
      (node (ref "R32") (pin "2") (pinfunction "2_2") (pintype "passive"))
    )
    (net (code "56") (name "Net-(IC7-OUT)") (class "Default")
      (node (ref "IC7") (pin "4") (pinfunction "OUT_4") (pintype "output"))
      (node (ref "R31") (pin "2") (pinfunction "2_2") (pintype "passive"))
      (node (ref "R43") (pin "1") (pinfunction "1_1") (pintype "passive"))
    )
    (net (code "57") (name "Net-(Q1-B)") (class "Default")
      (node (ref "Q1") (pin "1") (pinfunction "B_1") (pintype "passive"))
      (node (ref "R13") (pin "1") (pinfunction "1_1") (pintype "passive"))
      (node (ref "R14") (pin "1") (pinfunction "1_1") (pintype "passive"))
    )
    (net (code "58") (name "Net-(Q2-B)") (class "Default")
      (node (ref "Q2") (pin "1") (pinfunction "B_1") (pintype "passive"))
      (node (ref "R17") (pin "1") (pinfunction "1_1") (pintype "passive"))
      (node (ref "R18") (pin "1") (pinfunction "1_1") (pintype "passive"))
    )
    (net (code "59") (name "Net-(Q3-B)") (class "Default")
      (node (ref "Q3") (pin "1") (pinfunction "B_1") (pintype "passive"))
      (node (ref "R21") (pin "1") (pinfunction "1_1") (pintype "passive"))
      (node (ref "R22") (pin "1") (pinfunction "1_1") (pintype "passive"))
    )
    (net (code "60") (name "Net-(Q4-B)") (class "Default")
      (node (ref "Q4") (pin "1") (pinfunction "B_1") (pintype "passive"))
      (node (ref "R23") (pin "1") (pinfunction "1_1") (pintype "passive"))
      (node (ref "R24") (pin "1") (pinfunction "1_1") (pintype "passive"))
    )
    (net (code "61") (name "Net-(TEENSY-9{slash}RX2{slash}PWM)") (class "Default")
      (node (ref "R41") (pin "2") (pinfunction "2_2") (pintype "passive"))
      (node (ref "TEENSY") (pin "9") (pinfunction "9/RX2/PWM_9") (pintype "bidirectional"))
    )
    (net (code "62") (name "Net-(U1-EN)") (class "Default")
      (node (ref "C10") (pin "1") (pinfunction "1_1") (pintype "passive"))
      (node (ref "C8") (pin "1") (pinfunction "1_1") (pintype "passive"))
      (node (ref "L1") (pin "2") (pinfunction "2_2") (pintype "passive"))
      (node (ref "U1") (pin "1") (pinfunction "VIN_1") (pintype "input"))
      (node (ref "U1") (pin "3") (pinfunction "EN_3") (pintype "input"))
    )
    (net (code "63") (name "Net-(U3-~{RST})") (class "Default")
      (node (ref "R40") (pin "1") (pinfunction "1_1") (pintype "passive"))
      (node (ref "U3") (pin "13") (pinfunction "~{RST}_13") (pintype "input"))
    )
    (net (code "64") (name "RST") (class "Default")
      (node (ref "J3") (pin "8") (pinfunction "8_8") (pintype "passive"))
      (node (ref "TEENSY") (pin "7") (pinfunction "7/RX3_7") (pintype "bidirectional"))
    )
    (net (code "65") (name "SCK") (class "Default")
      (node (ref "J3") (pin "6") (pinfunction "6_6") (pintype "passive"))
      (node (ref "TEENSY") (pin "13") (pinfunction "13/SCK/LED_13") (pintype "bidirectional"))
      (node (ref "U3") (pin "10") (pinfunction "SCLK_10") (pintype "input"))
    )
    (net (code "66") (name "SW_B") (class "Default")
      (node (ref "J4") (pin "1") (pinfunction "1_1") (pintype "passive"))
      (node (ref "TEENSY") (pin "4") (pinfunction "4/CAN-RX/PWM_4") (pintype "bidirectional"))
    )
    (net (code "67") (name "SW_L") (class "Default")
      (node (ref "J2") (pin "4") (pinfunction "4_4") (pintype "passive"))
      (node (ref "TEENSY") (pin "23/A9") (pinfunction "23/A9/T/PWM_23/A9") (pintype "bidirectional"))
    )
    (net (code "68") (name "SW_R") (class "Default")
      (node (ref "J4") (pin "4") (pinfunction "4_4") (pintype "passive"))
      (node (ref "TEENSY") (pin "14/A0") (pinfunction "14/A0_14/A0") (pintype "bidirectional"))
    )
    (net (code "69") (name "SW_T") (class "Default")
      (node (ref "J2") (pin "1") (pinfunction "1_1") (pintype "passive"))
      (node (ref "TEENSY") (pin "5") (pinfunction "5/PWM_5") (pintype "bidirectional"))
    )
    (net (code "70") (name "TR_I1") (class "Default")
      (node (ref "J1") (pin "2") (pinfunction "2_2") (pintype "passive"))
      (node (ref "R13") (pin "2") (pinfunction "2_2") (pintype "passive"))
    )
    (net (code "71") (name "TR_I2") (class "Default")
      (node (ref "J1") (pin "4") (pinfunction "4_4") (pintype "passive"))
      (node (ref "R17") (pin "2") (pinfunction "2_2") (pintype "passive"))
    )
    (net (code "72") (name "TR_I3") (class "Default")
      (node (ref "J1") (pin "6") (pinfunction "6_6") (pintype "passive"))
      (node (ref "R22") (pin "2") (pinfunction "2_2") (pintype "passive"))
    )
    (net (code "73") (name "TR_I4") (class "Default")
      (node (ref "J1") (pin "8") (pinfunction "8_8") (pintype "passive"))
      (node (ref "R23") (pin "2") (pinfunction "2_2") (pintype "passive"))
    )
    (net (code "74") (name "T_DAC") (class "Default")
      (node (ref "IC7") (pin "1") (pinfunction "+IN_1") (pintype "input"))
      (node (ref "TEENSY") (pin "RESET/DAC") (pinfunction "A14/DAC_RESET/DAC") (pintype "bidirectional"))
    )
    (net (code "75") (name "VCC") (class "Default")
      (node (ref "C13") (pin "+") (pinfunction "+_+") (pintype "passive"))
      (node (ref "C19") (pin "+") (pinfunction "+_+") (pintype "passive"))
      (node (ref "C22") (pin "2") (pinfunction "2_2") (pintype "passive"))
      (node (ref "C27") (pin "1") (pinfunction "1_1") (pintype "passive"))
      (node (ref "C29") (pin "1") (pinfunction "1_1") (pintype "passive"))
      (node (ref "D1") (pin "C") (pinfunction "C_C") (pintype "passive"))
      (node (ref "IC5") (pin "8") (pinfunction "V+_8") (pintype "power_in"))
      (node (ref "IC6") (pin "8") (pinfunction "V+_8") (pintype "power_in"))
      (node (ref "IC7") (pin "5") (pinfunction "V+_5") (pintype "power_in"))
      (node (ref "U2") (pin "3") (pinfunction "IN_3") (pintype "input"))
    )
    (net (code "76") (name "VEE") (class "Default")
      (node (ref "C14") (pin "1") (pinfunction "1_1") (pintype "passive"))
      (node (ref "C18") (pin "-") (pinfunction "-_-") (pintype "passive"))
      (node (ref "C23") (pin "2") (pinfunction "2_2") (pintype "passive"))
      (node (ref "C26") (pin "2") (pinfunction "2_2") (pintype "passive"))
      (node (ref "C31") (pin "2") (pinfunction "2_2") (pintype "passive"))
      (node (ref "D2") (pin "A") (pinfunction "A_A") (pintype "passive"))
      (node (ref "IC5") (pin "4") (pinfunction "V-_4") (pintype "power_in"))
      (node (ref "IC6") (pin "4") (pinfunction "V-_4") (pintype "power_in"))
      (node (ref "IC7") (pin "2") (pinfunction "V-_2") (pintype "power_in"))
      (node (ref "R25") (pin "1") (pinfunction "1_1") (pintype "passive"))
    )
    (net (code "77") (name "V_BIAS") (class "Default")
      (node (ref "C21") (pin "1") (pinfunction "1_1") (pintype "passive"))
      (node (ref "C40") (pin "+") (pinfunction "+_+") (pintype "passive"))
      (node (ref "IC5") (pin "3") (pinfunction "+IN_3") (pintype "input"))
      (node (ref "IC5") (pin "5") (pinfunction "+IN_5") (pintype "input"))
      (node (ref "IC6") (pin "3") (pinfunction "+IN_3") (pintype "input"))
      (node (ref "IC6") (pin "5") (pinfunction "+IN_5") (pintype "input"))
      (node (ref "R42") (pin "2") (pinfunction "2_2") (pintype "passive"))
    )
    (net (code "78") (name "unconnected-(U3-VREFH{slash}VREFOUT-Pad3)") (class "Default")
      (node (ref "U3") (pin "3") (pinfunction "VREFH/VREFOUT_3") (pintype "bidirectional"))
    )
  )
)
